# mcu.net
KiCad netlist of a schematic drawn in Altium Designer
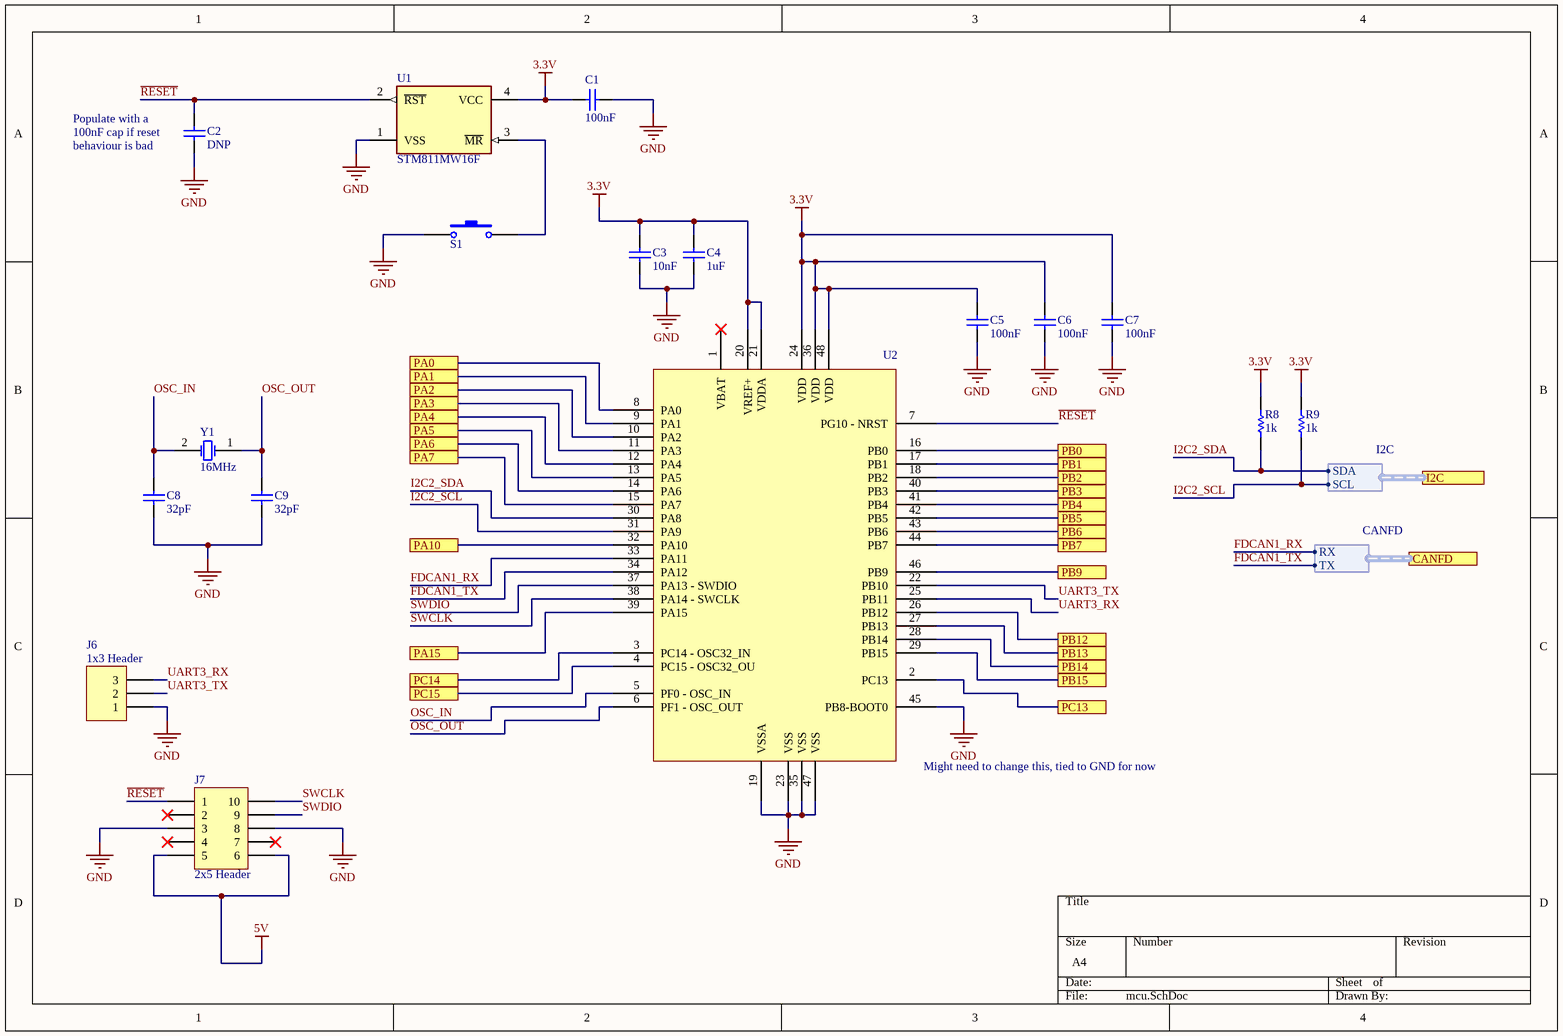
[diagram p0: mcu.SchDoc]

(export (version "E")
  (design (tool "Eeschema 10.0.6"))
  (components
    (comp (ref "C1")
      (value "100nF")
      (footprint "0603 - Capacitor")
      (description "Nonpolarized Capacitor")
      (fields (field (name "Comment") "Capacitor - Nonpolarized"))
      (libsource (lib "General") (part "Capacitor - Nonpolarized"))
    )
    (comp (ref "C2")
      (value "DNP")
      (footprint "0603 - Capacitor")
      (description "Nonpolarized Capacitor")
      (fields (field (name "Comment") "Capacitor - Nonpolarized"))
      (libsource (lib "General") (part "Capacitor - Nonpolarized"))
    )
    (comp (ref "C3")
      (value "10nF")
      (footprint "0603 - Capacitor")
      (description "Nonpolarized Capacitor")
      (fields (field (name "Comment") "Capacitor - Nonpolarized"))
      (libsource (lib "General") (part "Capacitor - Nonpolarized"))
    )
    (comp (ref "C4")
      (value "1uF")
      (footprint "0603 - Capacitor")
      (description "Nonpolarized Capacitor")
      (fields (field (name "Comment") "Capacitor - Nonpolarized"))
      (libsource (lib "General") (part "Capacitor - Nonpolarized"))
    )
    (comp (ref "C5")
      (value "100nF")
      (footprint "0603 - Capacitor")
      (description "Nonpolarized Capacitor")
      (fields (field (name "Comment") "Capacitor - Nonpolarized"))
      (libsource (lib "General") (part "Capacitor - Nonpolarized"))
    )
    (comp (ref "C6")
      (value "100nF")
      (footprint "0603 - Capacitor")
      (description "Nonpolarized Capacitor")
      (fields (field (name "Comment") "Capacitor - Nonpolarized"))
      (libsource (lib "General") (part "Capacitor - Nonpolarized"))
    )
    (comp (ref "C7")
      (value "100nF")
      (footprint "0603 - Capacitor")
      (description "Nonpolarized Capacitor")
      (fields (field (name "Comment") "Capacitor - Nonpolarized"))
      (libsource (lib "General") (part "Capacitor - Nonpolarized"))
    )
    (comp (ref "C8")
      (value "32pF")
      (footprint "0603 - Capacitor")
      (description "Nonpolarized Capacitor")
      (fields (field (name "Comment") "Capacitor - Nonpolarized"))
      (libsource (lib "General") (part "Capacitor - Nonpolarized"))
    )
    (comp (ref "C9")
      (value "32pF")
      (footprint "0603 - Capacitor")
      (description "Nonpolarized Capacitor")
      (fields (field (name "Comment") "Capacitor - Nonpolarized"))
      (libsource (lib "General") (part "Capacitor - Nonpolarized"))
    )
    (comp (ref "J6")
      (value "1x3 Header")
      (footprint "HDR1X3")
      (description "1x3 Pin Header")
      (libsource (lib "GeneralConnectors") (part "1x3 Header"))
    )
    (comp (ref "J7")
      (value "2x5 Header")
      (footprint "HDR2x5")
      (description "2x5 Pin Header")
      (libsource (lib "GeneralConnectors") (part "2x5 Header"))
    )
    (comp (ref "R8")
      (value "1k")
      (footprint "0603 - Resistor")
      (description "Resistor")
      (libsource (lib "General") (part "Resistor"))
    )
    (comp (ref "R9")
      (value "1k")
      (footprint "0603 - Resistor")
      (description "Resistor")
      (libsource (lib "General") (part "Resistor"))
    )
    (comp (ref "S1")
      (value "Switch - Push Button")
      (footprint "6x6mm Switch")
      (description "Push Button Switch")
      (libsource (lib "General") (part "Switch - Push Button"))
    )
    (comp (ref "U1")
      (value "STM811MW16F")
      (footprint "FP-SOT143-4-MFG")
      (description "IC MPU RESET CIRC 4.38V SOT143-4")
      (fields
        (field (name "OCTOPART") "https://octopart.com/stm811mw16f-stmicroelectronics-506032")
        (field (name "MANUFACTURER") "STMicroelectronics")
      )
      (libsource (lib "Altium Content Vault") (part "f524d9b186a75d434dc584b5d451434"))
    )
    (comp (ref "U2")
      (value "STM32G431C6T6")
      (footprint "TSQFP50P900X900X160-48N")
      (description "MCU 32BIT 32KB FLASH 48LQFP")
      (fields (field (name "MANUFACTURER") "ST"))
      (libsource (lib "GeneralComponents") (part "STM32G431C6T6"))
    )
    (comp (ref "Y1")
      (value "16MHz")
      (footprint "2-SMD NO LEAD CRSYSTAL")
      (description "Crystal Oscillator")
      (fields (field (name "Comment") "Oscillator"))
      (libsource (lib "General") (part "Oscillator"))
    )
  )
  (nets
    (net (code "3") (name "/FDCAN1_RX") (class "Default")
      (node (ref "U2") (pin "33") (pinfunction "PA11_33") (pintype "passive"))
    )
    (net (code "4") (name "/FDCAN1_TX") (class "Default")
      (node (ref "U2") (pin "34") (pinfunction "PA12_34") (pintype "passive"))
    )
    (net (code "5") (name "/I2C2_SCL") (class "Default")
      (node (ref "R9") (pin "1") (pinfunction "1_1") (pintype "passive"))
      (node (ref "U2") (pin "31") (pinfunction "PA9_31") (pintype "passive"))
    )
    (net (code "6") (name "/I2C2_SDA") (class "Default")
      (node (ref "R8") (pin "1") (pinfunction "1_1") (pintype "passive"))
      (node (ref "U2") (pin "30") (pinfunction "PA8_30") (pintype "passive"))
    )
    (net (code "7") (name "/OSC_IN") (class "Default")
      (node (ref "C8") (pin "2") (pinfunction "2_2") (pintype "passive"))
      (node (ref "U2") (pin "5") (pinfunction "PF0_-_OSC_IN_5") (pintype "passive"))
      (node (ref "Y1") (pin "2") (pinfunction "OSC2_2") (pintype "passive"))
    )
    (net (code "8") (name "/OSC_OUT") (class "Default")
      (node (ref "C9") (pin "2") (pinfunction "2_2") (pintype "passive"))
      (node (ref "U2") (pin "6") (pinfunction "PF1_-_OSC_OUT_6") (pintype "passive"))
      (node (ref "Y1") (pin "1") (pinfunction "OSC1_1") (pintype "passive"))
    )
    (net (code "9") (name "/PA0") (class "Default")
      (node (ref "U2") (pin "8") (pinfunction "PA0_8") (pintype "passive"))
    )
    (net (code "10") (name "/PA1") (class "Default")
      (node (ref "U2") (pin "9") (pinfunction "PA1_9") (pintype "passive"))
    )
    (net (code "11") (name "/PA2") (class "Default")
      (node (ref "U2") (pin "10") (pinfunction "PA2_10") (pintype "passive"))
    )
    (net (code "12") (name "/PA3") (class "Default")
      (node (ref "U2") (pin "11") (pinfunction "PA3_11") (pintype "passive"))
    )
    (net (code "13") (name "/PA4") (class "Default")
      (node (ref "U2") (pin "12") (pinfunction "PA4_12") (pintype "passive"))
    )
    (net (code "14") (name "/PA5") (class "Default")
      (node (ref "U2") (pin "13") (pinfunction "PA5_13") (pintype "passive"))
    )
    (net (code "15") (name "/PA6") (class "Default")
      (node (ref "U2") (pin "14") (pinfunction "PA6_14") (pintype "passive"))
    )
    (net (code "16") (name "/PA7") (class "Default")
      (node (ref "U2") (pin "15") (pinfunction "PA7_15") (pintype "passive"))
    )
    (net (code "17") (name "/PA10") (class "Default")
      (node (ref "U2") (pin "32") (pinfunction "PA10_32") (pintype "passive"))
    )
    (net (code "18") (name "/PA15") (class "Default")
      (node (ref "U2") (pin "39") (pinfunction "PA15_39") (pintype "passive"))
    )
    (net (code "19") (name "/PB0") (class "Default")
      (node (ref "U2") (pin "16") (pinfunction "PB0_16") (pintype "passive"))
    )
    (net (code "20") (name "/PB1") (class "Default")
      (node (ref "U2") (pin "17") (pinfunction "PB1_17") (pintype "passive"))
    )
    (net (code "21") (name "/PB2") (class "Default")
      (node (ref "U2") (pin "18") (pinfunction "PB2_18") (pintype "passive"))
    )
    (net (code "22") (name "/PB3") (class "Default")
      (node (ref "U2") (pin "40") (pinfunction "PB3_40") (pintype "passive"))
    )
    (net (code "23") (name "/PB4") (class "Default")
      (node (ref "U2") (pin "41") (pinfunction "PB4_41") (pintype "passive"))
    )
    (net (code "24") (name "/PB5") (class "Default")
      (node (ref "U2") (pin "42") (pinfunction "PB5_42") (pintype "passive"))
    )
    (net (code "25") (name "/PB6") (class "Default")
      (node (ref "U2") (pin "43") (pinfunction "PB6_43") (pintype "passive"))
    )
    (net (code "26") (name "/PB7") (class "Default")
      (node (ref "U2") (pin "44") (pinfunction "PB7_44") (pintype "passive"))
    )
    (net (code "27") (name "/PB9") (class "Default")
      (node (ref "U2") (pin "46") (pinfunction "PB9_46") (pintype "passive"))
    )
    (net (code "28") (name "/PB12") (class "Default")
      (node (ref "U2") (pin "26") (pinfunction "PB12_26") (pintype "passive"))
    )
    (net (code "29") (name "/PB13") (class "Default")
      (node (ref "U2") (pin "27") (pinfunction "PB13_27") (pintype "passive"))
    )
    (net (code "30") (name "/PB14") (class "Default")
      (node (ref "U2") (pin "28") (pinfunction "PB14_28") (pintype "passive"))
    )
    (net (code "31") (name "/PB15") (class "Default")
      (node (ref "U2") (pin "29") (pinfunction "PB15_29") (pintype "passive"))
    )
    (net (code "32") (name "/PC13") (class "Default")
      (node (ref "U2") (pin "2") (pinfunction "PC13_2") (pintype "passive"))
    )
    (net (code "33") (name "/PC14") (class "Default")
      (node (ref "U2") (pin "3") (pinfunction "PC14_-_OSC32_IN_3") (pintype "passive"))
    )
    (net (code "34") (name "/PC15") (class "Default")
      (node (ref "U2") (pin "4") (pinfunction "PC15_-_OSC32_OU_4") (pintype "passive"))
    )
    (net (code "35") (name "/SWCLK") (class "Default")
      (node (ref "J7") (pin "10") (pinfunction "10_10") (pintype "passive"))
      (node (ref "U2") (pin "38") (pinfunction "PA14_-_SWCLK_38") (pintype "passive"))
    )
    (net (code "36") (name "/SWDIO") (class "Default")
      (node (ref "J7") (pin "9") (pinfunction "9_9") (pintype "passive"))
      (node (ref "U2") (pin "37") (pinfunction "PA13_-_SWDIO_37") (pintype "passive"))
    )
    (net (code "37") (name "/UART3_RX") (class "Default")
      (node (ref "J6") (pin "3") (pinfunction "3_3") (pintype "passive"))
      (node (ref "U2") (pin "25") (pinfunction "PB11_25") (pintype "passive"))
    )
    (net (code "38") (name "/UART3_TX") (class "Default")
      (node (ref "J6") (pin "2") (pinfunction "2_2") (pintype "passive"))
      (node (ref "U2") (pin "22") (pinfunction "PB10_22") (pintype "passive"))
    )
    (net (code "41") (name "/~{RESET}") (class "Default")
      (node (ref "C2") (pin "2") (pinfunction "2_2") (pintype "passive"))
      (node (ref "J7") (pin "1") (pinfunction "1_1") (pintype "passive"))
      (node (ref "U1") (pin "2") (pinfunction "~{RST}_2") (pintype "output"))
      (node (ref "U2") (pin "7") (pinfunction "PG10_-_NRST_7") (pintype "passive"))
    )
    (net (code "42") (name "3.3V") (class "Default")
      (node (ref "C1") (pin "2") (pinfunction "2_2") (pintype "passive"))
      (node (ref "C3") (pin "2") (pinfunction "2_2") (pintype "passive"))
      (node (ref "C4") (pin "2") (pinfunction "2_2") (pintype "passive"))
      (node (ref "C5") (pin "2") (pinfunction "2_2") (pintype "passive"))
      (node (ref "C6") (pin "2") (pinfunction "2_2") (pintype "passive"))
      (node (ref "C7") (pin "2") (pinfunction "2_2") (pintype "passive"))
      (node (ref "R8") (pin "2") (pinfunction "2_2") (pintype "passive"))
      (node (ref "R9") (pin "2") (pinfunction "2_2") (pintype "passive"))
      (node (ref "U1") (pin "4") (pinfunction "VCC_4") (pintype "power_in"))
      (node (ref "U2") (pin "20") (pinfunction "VREF+_20") (pintype "power_in"))
      (node (ref "U2") (pin "21") (pinfunction "VDDA_21") (pintype "power_in"))
      (node (ref "U2") (pin "24") (pinfunction "VDD_24") (pintype "power_in"))
      (node (ref "U2") (pin "36") (pinfunction "VDD_36") (pintype "power_in"))
      (node (ref "U2") (pin "48") (pinfunction "VDD_48") (pintype "power_in"))
    )
    (net (code "43") (name "5V") (class "Default")
      (node (ref "J7") (pin "5") (pinfunction "5_5") (pintype "passive"))
      (node (ref "J7") (pin "6") (pinfunction "6_6") (pintype "passive"))
    )
    (net (code "44") (name "GND") (class "Default")
      (node (ref "C1") (pin "1") (pinfunction "1_1") (pintype "passive"))
      (node (ref "C2") (pin "1") (pinfunction "1_1") (pintype "passive"))
      (node (ref "C3") (pin "1") (pinfunction "1_1") (pintype "passive"))
      (node (ref "C4") (pin "1") (pinfunction "1_1") (pintype "passive"))
      (node (ref "C5") (pin "1") (pinfunction "1_1") (pintype "passive"))
      (node (ref "C6") (pin "1") (pinfunction "1_1") (pintype "passive"))
      (node (ref "C7") (pin "1") (pinfunction "1_1") (pintype "passive"))
      (node (ref "C8") (pin "1") (pinfunction "1_1") (pintype "passive"))
      (node (ref "C9") (pin "1") (pinfunction "1_1") (pintype "passive"))
      (node (ref "J6") (pin "1") (pinfunction "1_1") (pintype "passive"))
      (node (ref "J7") (pin "3") (pinfunction "3_3") (pintype "passive"))
      (node (ref "J7") (pin "8") (pinfunction "8_8") (pintype "passive"))
      (node (ref "S1") (pin "2") (pinfunction "2_2") (pintype "passive"))
      (node (ref "U1") (pin "1") (pinfunction "VSS_1") (pintype "power_in"))
      (node (ref "U2") (pin "19") (pinfunction "VSSA_19") (pintype "power_in"))
      (node (ref "U2") (pin "23") (pinfunction "VSS_23") (pintype "power_in"))
      (node (ref "U2") (pin "35") (pinfunction "VSS_35") (pintype "power_in"))
      (node (ref "U2") (pin "45") (pinfunction "PB8-BOOT0_45") (pintype "passive"))
      (node (ref "U2") (pin "47") (pinfunction "VSS_47") (pintype "power_in"))
    )
    (net (code "45") (name "Net-(U1-~{MR})") (class "Default")
      (node (ref "S1") (pin "1") (pinfunction "1_1") (pintype "passive"))
      (node (ref "U1") (pin "3") (pinfunction "~{MR}_3") (pintype "input"))
    )
    (net (code "46") (name "unconnected-(J7-Pad2)") (class "Default")
      (node (ref "J7") (pin "2") (pinfunction "2_2") (pintype "passive+no_connect"))
    )
    (net (code "47") (name "unconnected-(J7-Pad4)") (class "Default")
      (node (ref "J7") (pin "4") (pinfunction "4_4") (pintype "passive+no_connect"))
    )
    (net (code "48") (name "unconnected-(J7-Pad7)") (class "Default")
      (node (ref "J7") (pin "7") (pinfunction "7_7") (pintype "passive+no_connect"))
    )
    (net (code "49") (name "unconnected-(U2-VBAT-Pad1)") (class "Default")
      (node (ref "U2") (pin "1") (pinfunction "VBAT_1") (pintype "power_in+no_connect"))
    )
  )
)
